# template.net
KiCad netlist of a schematic drawn in Altium Designer
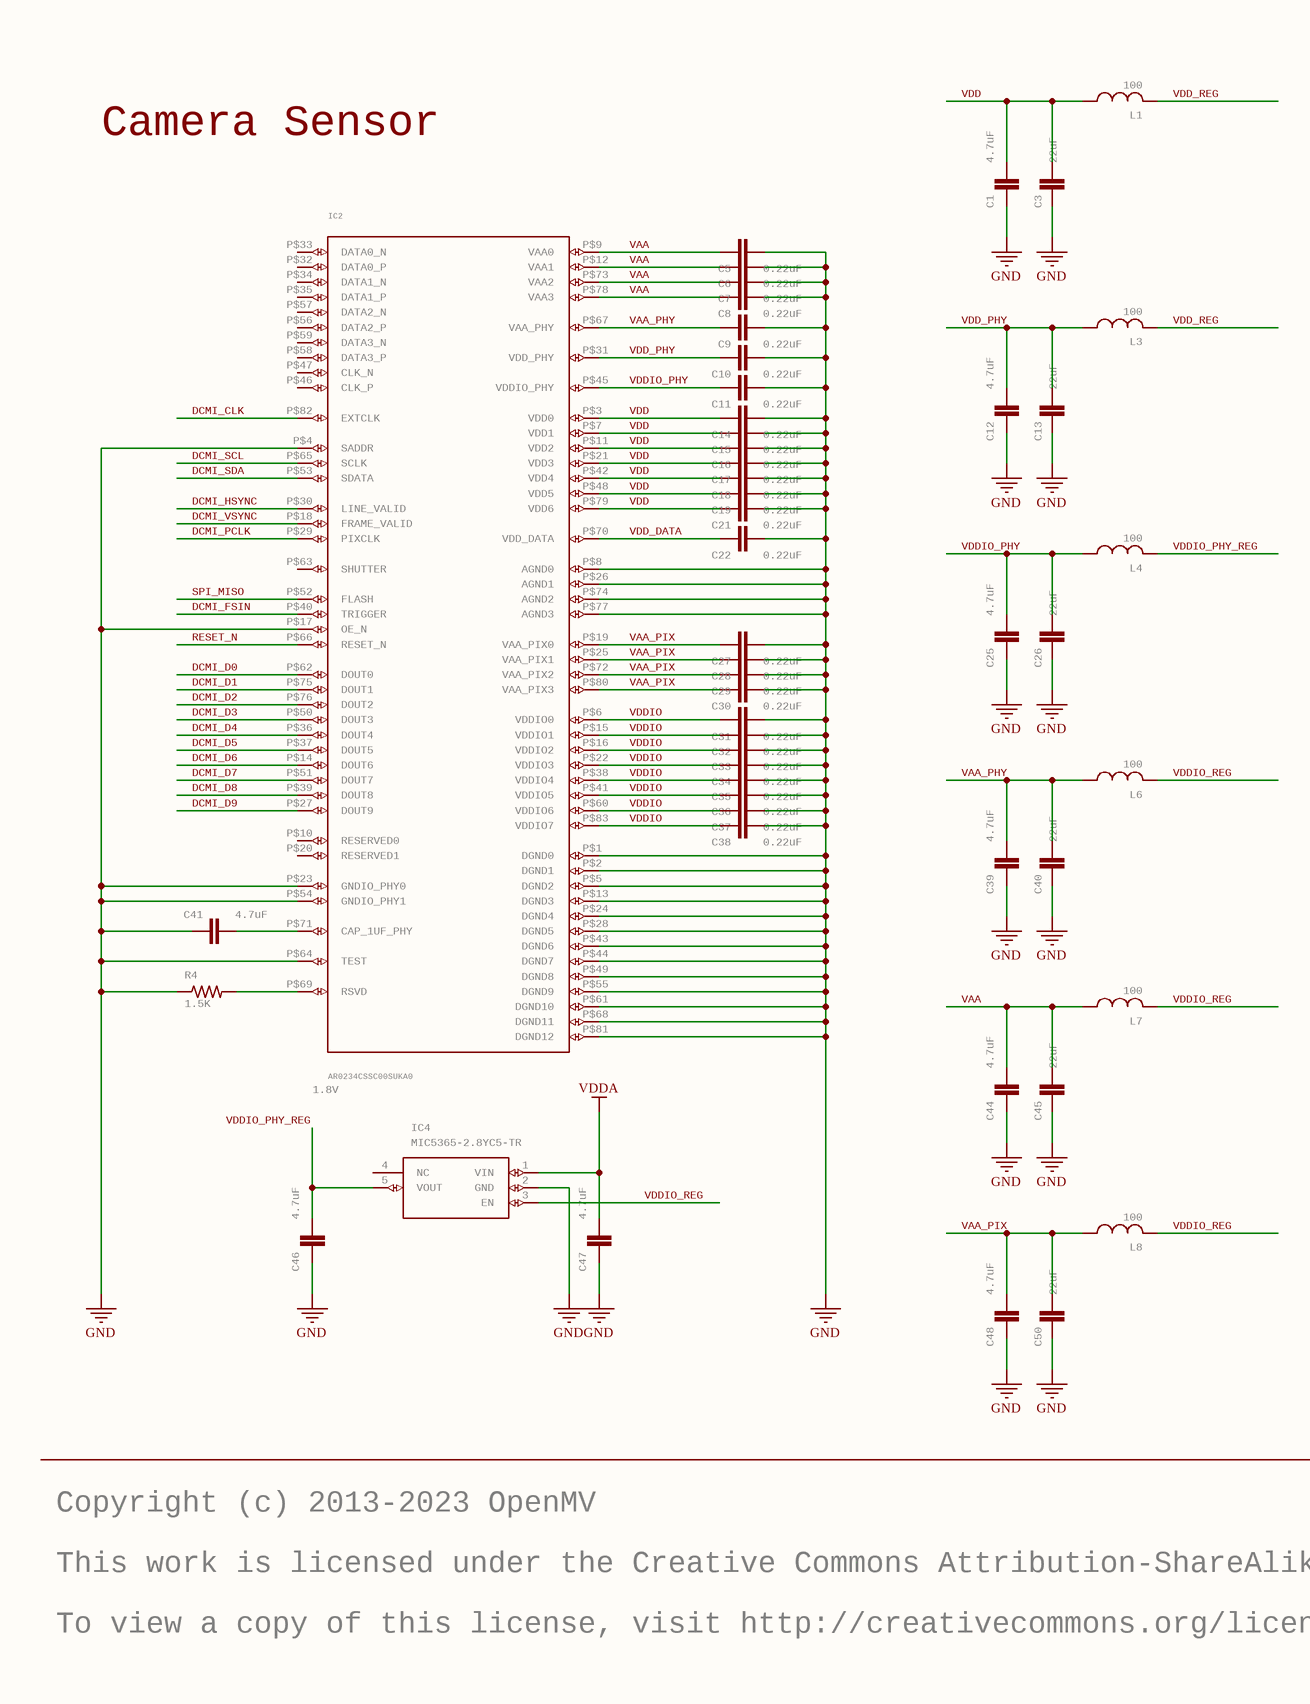
[diagram p0: template.SchDoc, left]
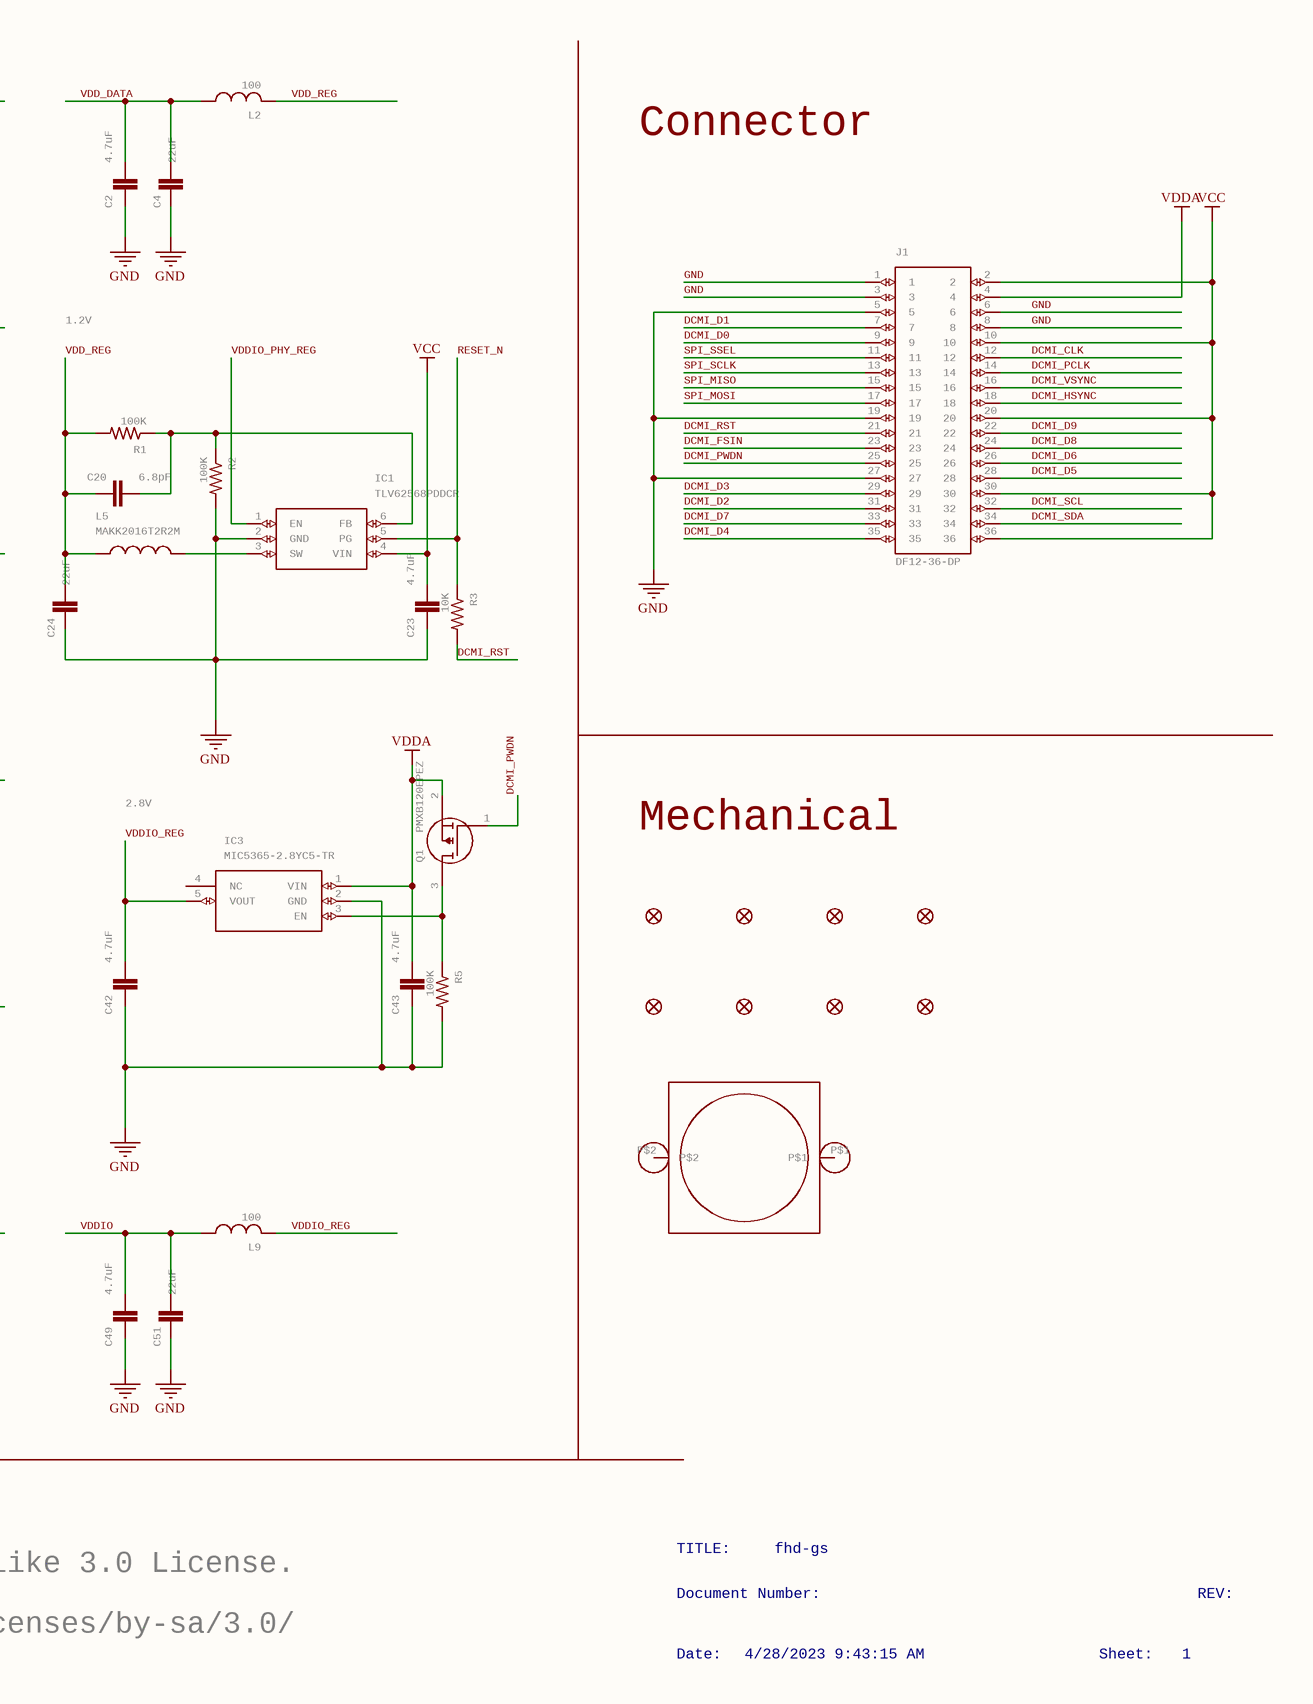
[diagram p1: template.SchDoc, right]

(export (version "E")
  (design (tool "Eeschema 10.0.6"))
  (components
    (comp (ref "C1")
      (value "4.7uF")
      (footprint "0402")
      (description "0402 (1005 Metric) Nick Garner - TeleSense")
      (fields (field (name "MPN") "JMK105BBJ475MV-F"))
      (libsource (lib "") (part "CAP_0402_1"))
    )
    (comp (ref "C2")
      (value "4.7uF")
      (footprint "0402")
      (description "0402 (1005 Metric) Nick Garner - TeleSense")
      (fields (field (name "MPN") "JMK105BBJ475MV-F"))
      (libsource (lib "") (part "CAP_0402_1"))
    )
    (comp (ref "C3")
      (value "22uF")
      (footprint "0805")
      (fields (field (name "MPN") "CL21A226MQQNNNE"))
      (libsource (lib "SparkFun-Capacitors") (part "22UF-0805-6.3V-20%"))
    )
    (comp (ref "C4")
      (value "22uF")
      (footprint "0805")
      (fields (field (name "MPN") "CL21A226MQQNNNE"))
      (libsource (lib "SparkFun-Capacitors") (part "22UF-0805-6.3V-20%"))
    )
    (comp (ref "C5")
      (value "0.22uF")
      (footprint "C0201")
      (description "CAPACITOR, European symbol")
      (fields (field (name "MPN") "GRM033R60J224ME15D"))
      (libsource (lib "rcl") (part "C-EUC0201"))
    )
    (comp (ref "C6")
      (value "0.22uF")
      (footprint "C0201")
      (description "CAPACITOR, European symbol")
      (fields (field (name "MPN") "GRM033R60J224ME15D"))
      (libsource (lib "rcl") (part "C-EUC0201"))
    )
    (comp (ref "C7")
      (value "0.22uF")
      (footprint "C0201")
      (description "CAPACITOR, European symbol")
      (fields (field (name "MPN") "GRM033R60J224ME15D"))
      (libsource (lib "rcl") (part "C-EUC0201"))
    )
    (comp (ref "C8")
      (value "0.22uF")
      (footprint "C0201")
      (description "CAPACITOR, European symbol")
      (fields (field (name "MPN") "GRM033R60J224ME15D"))
      (libsource (lib "rcl") (part "C-EUC0201"))
    )
    (comp (ref "C9")
      (value "0.22uF")
      (footprint "C0201")
      (description "CAPACITOR, European symbol")
      (fields (field (name "MPN") "GRM033R60J224ME15D"))
      (libsource (lib "rcl") (part "C-EUC0201"))
    )
    (comp (ref "C10")
      (value "0.22uF")
      (footprint "C0201")
      (description "CAPACITOR, European symbol")
      (fields (field (name "MPN") "GRM033R60J224ME15D"))
      (libsource (lib "rcl") (part "C-EUC0201"))
    )
    (comp (ref "C11")
      (value "0.22uF")
      (footprint "C0201")
      (description "CAPACITOR, European symbol")
      (fields (field (name "MPN") "GRM033R60J224ME15D"))
      (libsource (lib "rcl") (part "C-EUC0201"))
    )
    (comp (ref "C12")
      (value "4.7uF")
      (footprint "0402")
      (description "0402 (1005 Metric) Nick Garner - TeleSense")
      (fields (field (name "MPN") "JMK105BBJ475MV-F"))
      (libsource (lib "") (part "CAP_0402_1"))
    )
    (comp (ref "C13")
      (value "22uF")
      (footprint "0805")
      (fields (field (name "MPN") "CL21A226MQQNNNE"))
      (libsource (lib "SparkFun-Capacitors") (part "22UF-0805-6.3V-20%"))
    )
    (comp (ref "C14")
      (value "0.22uF")
      (footprint "C0201")
      (description "CAPACITOR, European symbol")
      (fields (field (name "MPN") "GRM033R60J224ME15D"))
      (libsource (lib "rcl") (part "C-EUC0201"))
    )
    (comp (ref "C15")
      (value "0.22uF")
      (footprint "C0201")
      (description "CAPACITOR, European symbol")
      (fields (field (name "MPN") "GRM033R60J224ME15D"))
      (libsource (lib "rcl") (part "C-EUC0201"))
    )
    (comp (ref "C16")
      (value "0.22uF")
      (footprint "C0201")
      (description "CAPACITOR, European symbol")
      (fields (field (name "MPN") "GRM033R60J224ME15D"))
      (libsource (lib "rcl") (part "C-EUC0201"))
    )
    (comp (ref "C17")
      (value "0.22uF")
      (footprint "C0201")
      (description "CAPACITOR, European symbol")
      (fields (field (name "MPN") "GRM033R60J224ME15D"))
      (libsource (lib "rcl") (part "C-EUC0201"))
    )
    (comp (ref "C18")
      (value "0.22uF")
      (footprint "C0201")
      (description "CAPACITOR, European symbol")
      (fields (field (name "MPN") "GRM033R60J224ME15D"))
      (libsource (lib "rcl") (part "C-EUC0201"))
    )
    (comp (ref "C19")
      (value "0.22uF")
      (footprint "C0201")
      (description "CAPACITOR, European symbol")
      (fields (field (name "MPN") "GRM033R60J224ME15D"))
      (libsource (lib "rcl") (part "C-EUC0201"))
    )
    (comp (ref "C20")
      (value "6.8pF")
      (footprint "0402")
      (description "0402 (1005 Metric) Nick Garner - TeleSense")
      (fields (field (name "MPN") "GRM1555C1H6R8DA01D"))
      (libsource (lib "0402") (part "CAP_0402"))
    )
    (comp (ref "C21")
      (value "0.22uF")
      (footprint "C0201")
      (description "CAPACITOR, European symbol")
      (fields (field (name "MPN") "GRM033R60J224ME15D"))
      (libsource (lib "rcl") (part "C-EUC0201"))
    )
    (comp (ref "C22")
      (value "0.22uF")
      (footprint "C0201")
      (description "CAPACITOR, European symbol")
      (fields (field (name "MPN") "GRM033R60J224ME15D"))
      (libsource (lib "rcl") (part "C-EUC0201"))
    )
    (comp (ref "C23")
      (value "4.7uF")
      (footprint "0402")
      (description "0402 (1005 Metric) Nick Garner - TeleSense")
      (fields (field (name "MPN") "JMK105BBJ475MV-F"))
      (libsource (lib "") (part "CAP_0402_1"))
    )
    (comp (ref "C24")
      (value "22uF")
      (footprint "0805")
      (fields (field (name "MPN") "CL21A226MQQNNNE"))
      (libsource (lib "SparkFun-Capacitors") (part "22UF-0805-6.3V-20%"))
    )
    (comp (ref "C25")
      (value "4.7uF")
      (footprint "0402")
      (description "0402 (1005 Metric) Nick Garner - TeleSense")
      (fields (field (name "MPN") "JMK105BBJ475MV-F"))
      (libsource (lib "") (part "CAP_0402_1"))
    )
    (comp (ref "C26")
      (value "22uF")
      (footprint "0805")
      (fields (field (name "MPN") "CL21A226MQQNNNE"))
      (libsource (lib "SparkFun-Capacitors") (part "22UF-0805-6.3V-20%"))
    )
    (comp (ref "C27")
      (value "0.22uF")
      (footprint "C0201")
      (description "CAPACITOR, European symbol")
      (fields (field (name "MPN") "GRM033R60J224ME15D"))
      (libsource (lib "rcl") (part "C-EUC0201"))
    )
    (comp (ref "C28")
      (value "0.22uF")
      (footprint "C0201")
      (description "CAPACITOR, European symbol")
      (fields (field (name "MPN") "GRM033R60J224ME15D"))
      (libsource (lib "rcl") (part "C-EUC0201"))
    )
    (comp (ref "C29")
      (value "0.22uF")
      (footprint "C0201")
      (description "CAPACITOR, European symbol")
      (fields (field (name "MPN") "GRM033R60J224ME15D"))
      (libsource (lib "rcl") (part "C-EUC0201"))
    )
    (comp (ref "C30")
      (value "0.22uF")
      (footprint "C0201")
      (description "CAPACITOR, European symbol")
      (fields (field (name "MPN") "GRM033R60J224ME15D"))
      (libsource (lib "rcl") (part "C-EUC0201"))
    )
    (comp (ref "C31")
      (value "0.22uF")
      (footprint "C0201")
      (description "CAPACITOR, European symbol")
      (fields (field (name "MPN") "GRM033R60J224ME15D"))
      (libsource (lib "rcl") (part "C-EUC0201"))
    )
    (comp (ref "C32")
      (value "0.22uF")
      (footprint "C0201")
      (description "CAPACITOR, European symbol")
      (fields (field (name "MPN") "GRM033R60J224ME15D"))
      (libsource (lib "rcl") (part "C-EUC0201"))
    )
    (comp (ref "C33")
      (value "0.22uF")
      (footprint "C0201")
      (description "CAPACITOR, European symbol")
      (fields (field (name "MPN") "GRM033R60J224ME15D"))
      (libsource (lib "rcl") (part "C-EUC0201"))
    )
    (comp (ref "C34")
      (value "0.22uF")
      (footprint "C0201")
      (description "CAPACITOR, European symbol")
      (fields (field (name "MPN") "GRM033R60J224ME15D"))
      (libsource (lib "rcl") (part "C-EUC0201"))
    )
    (comp (ref "C35")
      (value "0.22uF")
      (footprint "C0201")
      (description "CAPACITOR, European symbol")
      (fields (field (name "MPN") "GRM033R60J224ME15D"))
      (libsource (lib "rcl") (part "C-EUC0201"))
    )
    (comp (ref "C36")
      (value "0.22uF")
      (footprint "C0201")
      (description "CAPACITOR, European symbol")
      (fields (field (name "MPN") "GRM033R60J224ME15D"))
      (libsource (lib "rcl") (part "C-EUC0201"))
    )
    (comp (ref "C37")
      (value "0.22uF")
      (footprint "C0201")
      (description "CAPACITOR, European symbol")
      (fields (field (name "MPN") "GRM033R60J224ME15D"))
      (libsource (lib "rcl") (part "C-EUC0201"))
    )
    (comp (ref "C38")
      (value "0.22uF")
      (footprint "C0201")
      (description "CAPACITOR, European symbol")
      (fields (field (name "MPN") "GRM033R60J224ME15D"))
      (libsource (lib "rcl") (part "C-EUC0201"))
    )
    (comp (ref "C39")
      (value "4.7uF")
      (footprint "0402")
      (description "0402 (1005 Metric) Nick Garner - TeleSense")
      (fields (field (name "MPN") "JMK105BBJ475MV-F"))
      (libsource (lib "") (part "CAP_0402_1"))
    )
    (comp (ref "C40")
      (value "22uF")
      (footprint "0805")
      (fields (field (name "MPN") "CL21A226MQQNNNE"))
      (libsource (lib "SparkFun-Capacitors") (part "22UF-0805-6.3V-20%"))
    )
    (comp (ref "C41")
      (value "4.7uF")
      (footprint "0402")
      (description "0402 (1005 Metric) Nick Garner - TeleSense")
      (fields (field (name "MPN") "JMK105BBJ475MV-F"))
      (libsource (lib "0402") (part "CAP_0402"))
    )
    (comp (ref "C42")
      (value "4.7uF")
      (footprint "0402")
      (description "0402 (1005 Metric) Nick Garner - TeleSense")
      (fields (field (name "MPN") "JMK105BBJ475MV-F"))
      (libsource (lib "") (part "CAP_0402_1"))
    )
    (comp (ref "C43")
      (value "4.7uF")
      (footprint "0402")
      (description "0402 (1005 Metric) Nick Garner - TeleSense")
      (fields (field (name "MPN") "JMK105BBJ475MV-F"))
      (libsource (lib "") (part "CAP_0402_1"))
    )
    (comp (ref "C44")
      (value "4.7uF")
      (footprint "0402")
      (description "0402 (1005 Metric) Nick Garner - TeleSense")
      (fields (field (name "MPN") "JMK105BBJ475MV-F"))
      (libsource (lib "") (part "CAP_0402_1"))
    )
    (comp (ref "C45")
      (value "22uF")
      (footprint "0805")
      (fields (field (name "MPN") "CL21A226MQQNNNE"))
      (libsource (lib "SparkFun-Capacitors") (part "22UF-0805-6.3V-20%"))
    )
    (comp (ref "C46")
      (value "4.7uF")
      (footprint "0402")
      (description "0402 (1005 Metric) Nick Garner - TeleSense")
      (fields (field (name "MPN") "JMK105BBJ475MV-F"))
      (libsource (lib "") (part "CAP_0402_1"))
    )
    (comp (ref "C47")
      (value "4.7uF")
      (footprint "0402")
      (description "0402 (1005 Metric) Nick Garner - TeleSense")
      (fields (field (name "MPN") "JMK105BBJ475MV-F"))
      (libsource (lib "") (part "CAP_0402_1"))
    )
    (comp (ref "C48")
      (value "4.7uF")
      (footprint "0402")
      (description "0402 (1005 Metric) Nick Garner - TeleSense")
      (fields (field (name "MPN") "JMK105BBJ475MV-F"))
      (libsource (lib "") (part "CAP_0402_1"))
    )
    (comp (ref "C49")
      (value "4.7uF")
      (footprint "0402")
      (description "0402 (1005 Metric) Nick Garner - TeleSense")
      (fields (field (name "MPN") "JMK105BBJ475MV-F"))
      (libsource (lib "") (part "CAP_0402_1"))
    )
    (comp (ref "C50")
      (value "22uF")
      (footprint "0805")
      (fields (field (name "MPN") "CL21A226MQQNNNE"))
      (libsource (lib "SparkFun-Capacitors") (part "22UF-0805-6.3V-20%"))
    )
    (comp (ref "C51")
      (value "22uF")
      (footprint "0805")
      (fields (field (name "MPN") "CL21A226MQQNNNE"))
      (libsource (lib "SparkFun-Capacitors") (part "22UF-0805-6.3V-20%"))
    )
    (comp (ref "FD1")
      (value "FIDUCIAL1X2")
      (footprint "FIDUCIAL-1X2")
      (fields (field (name "LIBRARYNAME") "SparkFun-Aesthetics"))
      (libsource (lib "SparkFun-Aesthetics") (part "FIDUCIAL1X2"))
    )
    (comp (ref "FD2")
      (value "FIDUCIAL1X2")
      (footprint "FIDUCIAL-1X2")
      (fields (field (name "LIBRARYNAME") "SparkFun-Aesthetics"))
      (libsource (lib "SparkFun-Aesthetics") (part "FIDUCIAL1X2"))
    )
    (comp (ref "FD3")
      (value "FIDUCIAL1X2")
      (footprint "FIDUCIAL-1X2")
      (fields (field (name "LIBRARYNAME") "SparkFun-Aesthetics"))
      (libsource (lib "SparkFun-Aesthetics") (part "FIDUCIAL1X2"))
    )
    (comp (ref "FD4")
      (value "FIDUCIAL1X2")
      (footprint "FIDUCIAL-1X2")
      (fields (field (name "LIBRARYNAME") "SparkFun-Aesthetics"))
      (libsource (lib "SparkFun-Aesthetics") (part "FIDUCIAL1X2"))
    )
    (comp (ref "FD5")
      (value "FIDUCIAL1X2")
      (footprint "FIDUCIAL-1X2")
      (fields (field (name "LIBRARYNAME") "SparkFun-Aesthetics"))
      (libsource (lib "SparkFun-Aesthetics") (part "FIDUCIAL1X2"))
    )
    (comp (ref "FD6")
      (value "FIDUCIAL1X2")
      (footprint "FIDUCIAL-1X2")
      (fields (field (name "LIBRARYNAME") "SparkFun-Aesthetics"))
      (libsource (lib "SparkFun-Aesthetics") (part "FIDUCIAL1X2"))
    )
    (comp (ref "FD7")
      (value "FIDUCIAL1X2")
      (footprint "FIDUCIAL-1X2")
      (fields (field (name "LIBRARYNAME") "SparkFun-Aesthetics"))
      (libsource (lib "SparkFun-Aesthetics") (part "FIDUCIAL1X2"))
    )
    (comp (ref "FD8")
      (value "FIDUCIAL1X2")
      (footprint "FIDUCIAL-1X2")
      (fields (field (name "LIBRARYNAME") "SparkFun-Aesthetics"))
      (libsource (lib "SparkFun-Aesthetics") (part "FIDUCIAL1X2"))
    )
    (comp (ref "H1")
      (value "LENSMOUNT20MM")
      (footprint "LENSMOUNT-20MM")
      (libsource (lib "lensmount") (part "LENSMOUNT20MM"))
    )
    (comp (ref "IC1")
      (value "TLV62568PDDCR")
      (footprint "SOT95P280X110-6N")
      (description "2.5V-5.5V input, 1A high efficiency step-down buck converter in SOT23 and SOT563 package")
      (fields (field (name "MOUSER_PART_NUMBER") "595-TLV62568PDDCR"))
      (libsource (lib "TLV62568PDDCR") (part "TLV62568PDDCR"))
    )
    (comp (ref "IC2")
      (value "AR0234CSSC00SUKA0")
      (footprint "AR0234CSSC00SUKA0")
      (libsource (lib "AR0234CSSC00SUKA0") (part "AR0234CSSC00SUKA0"))
    )
    (comp (ref "IC3")
      (value "MIC5365-2.8YC5-TR")
      (footprint "SOT65P210X110-5N")
      (description "IC REG LINEAR 2.8V 150MA SC70-5")
      (fields (field (name "MOUSER_PART_NUMBER") "998-MIC5365-2.8YC5TR"))
      (libsource (lib "MIC5365-2.8YC5-TR") (part "MIC5365-2.8YC5-TR"))
    )
    (comp (ref "IC4")
      (value "MIC5365-2.8YC5-TR")
      (footprint "SOT65P210X110-5N")
      (description "IC REG LINEAR 2.8V 150MA SC70-5")
      (fields (field (name "MOUSER_PART_NUMBER") "998-MIC5365-2.8YC5TR"))
      (libsource (lib "MIC5365-2.8YC5-TR") (part "MIC5365-2.8YC5-TR"))
    )
    (comp (ref "J1")
      (value "DF12-36-DP")
      (footprint "DF12-36-DP")
      (fields (field (name "MPN") "DF12NB(3.0)-36DP-0.5V(51)"))
      (libsource (lib "DF12NB(3.0)-36DP-0.5V(51)") (part "DF12-36-DP"))
    )
    (comp (ref "L1")
      (value "100")
      (footprint "0402")
      (fields (field (name "MPN") "MFBM1V1005-101-R"))
      (libsource (lib "0402") (part "INDUCTOR_0402"))
    )
    (comp (ref "L2")
      (value "100")
      (footprint "0402")
      (fields (field (name "MPN") "MFBM1V1005-101-R"))
      (libsource (lib "0402") (part "INDUCTOR_0402"))
    )
    (comp (ref "L3")
      (value "100")
      (footprint "0402")
      (fields (field (name "MPN") "MFBM1V1005-101-R"))
      (libsource (lib "0402") (part "INDUCTOR_0402"))
    )
    (comp (ref "L4")
      (value "100")
      (footprint "0402")
      (fields (field (name "MPN") "MFBM1V1005-101-R"))
      (libsource (lib "0402") (part "INDUCTOR_0402"))
    )
    (comp (ref "L5")
      (value "MAKK2016T2R2M")
      (footprint "INDC2016X100N")
      (description "2.2 µH Shielded Drum Core, Wirewound Inductor 1.5 A 160mOhm Max 0806 (2016 Metric)")
      (fields (field (name "MF") "Taiyo Yuden"))
      (libsource (lib "MAKK2016T2R2M") (part "MAKK2016T2R2M"))
    )
    (comp (ref "L6")
      (value "100")
      (footprint "0402")
      (fields (field (name "MPN") "MFBM1V1005-101-R"))
      (libsource (lib "0402") (part "INDUCTOR_0402"))
    )
    (comp (ref "L7")
      (value "100")
      (footprint "0402")
      (fields (field (name "MPN") "MFBM1V1005-101-R"))
      (libsource (lib "0402") (part "INDUCTOR_0402"))
    )
    (comp (ref "L8")
      (value "100")
      (footprint "0402")
      (fields (field (name "MPN") "MFBM1V1005-101-R"))
      (libsource (lib "0402") (part "INDUCTOR_0402"))
    )
    (comp (ref "L9")
      (value "100")
      (footprint "0402")
      (fields (field (name "MPN") "MFBM1V1005-101-R"))
      (libsource (lib "0402") (part "INDUCTOR_0402"))
    )
    (comp (ref "Q1")
      (value "PMXB120EPEZ")
      (footprint "PMXB120EPEZ")
      (description "MOSFET 30 V, P-channel Trench MOSFET")
      (fields (field (name "MOUSER_PART_NUMBER") "771-PMXB120EPEZ"))
      (libsource (lib "PMXB120EPEZ") (part "PMXB120EPEZ"))
    )
    (comp (ref "R1")
      (value "100K")
      (footprint "R0402")
      (description "RESISTOR, American symbol")
      (fields (field (name "MPN") "AC0402FR-07100KL"))
      (libsource (lib "rcl") (part "R-US_R0402"))
    )
    (comp (ref "R2")
      (value "100K")
      (footprint "R0402")
      (description "RESISTOR, American symbol")
      (fields (field (name "MPN") "AC0402FR-07100KL"))
      (libsource (lib "rcl") (part "R-US_R0402"))
    )
    (comp (ref "R3")
      (value "10K")
      (footprint "R0402")
      (description "RESISTOR, American symbol")
      (fields (field (name "MPN") "AC0402FR-1310KL"))
      (libsource (lib "rcl") (part "R-US_R0402"))
    )
    (comp (ref "R4")
      (value "1.5K")
      (footprint "R0402")
      (description "RESISTOR, American symbol")
      (fields (field (name "MPN") "RC0402FR-131K5L"))
      (libsource (lib "rcl") (part "R-US_R0402"))
    )
    (comp (ref "R5")
      (value "100K")
      (footprint "R0402")
      (description "RESISTOR, American symbol")
      (fields (field (name "MPN") "AC0402FR-07100KL"))
      (libsource (lib "rcl") (part "R-US_R0402"))
    )
  )
  (nets
    (net (code "1") (name "/DCMI_CLK") (class "Default")
      (node (ref "IC2") (pin "P$82") (pinfunction "EXTCLK_P$82") (pintype "bidirectional"))
      (node (ref "J1") (pin "12") (pinfunction "12_12") (pintype "bidirectional"))
    )
    (net (code "2") (name "/DCMI_D0") (class "Default")
      (node (ref "IC2") (pin "P$62") (pinfunction "DOUT0_P$62") (pintype "bidirectional"))
      (node (ref "J1") (pin "9") (pinfunction "9_9") (pintype "bidirectional"))
    )
    (net (code "3") (name "/DCMI_D1") (class "Default")
      (node (ref "IC2") (pin "P$75") (pinfunction "DOUT1_P$75") (pintype "bidirectional"))
      (node (ref "J1") (pin "7") (pinfunction "7_7") (pintype "bidirectional"))
    )
    (net (code "4") (name "/DCMI_D2") (class "Default")
      (node (ref "IC2") (pin "P$76") (pinfunction "DOUT2_P$76") (pintype "bidirectional"))
      (node (ref "J1") (pin "31") (pinfunction "31_31") (pintype "bidirectional"))
    )
    (net (code "5") (name "/DCMI_D3") (class "Default")
      (node (ref "IC2") (pin "P$50") (pinfunction "DOUT3_P$50") (pintype "bidirectional"))
      (node (ref "J1") (pin "29") (pinfunction "29_29") (pintype "bidirectional"))
    )
    (net (code "6") (name "/DCMI_D4") (class "Default")
      (node (ref "IC2") (pin "P$36") (pinfunction "DOUT4_P$36") (pintype "bidirectional"))
      (node (ref "J1") (pin "35") (pinfunction "35_35") (pintype "bidirectional"))
    )
    (net (code "7") (name "/DCMI_D5") (class "Default")
      (node (ref "IC2") (pin "P$37") (pinfunction "DOUT5_P$37") (pintype "bidirectional"))
      (node (ref "J1") (pin "28") (pinfunction "28_28") (pintype "bidirectional"))
    )
    (net (code "8") (name "/DCMI_D6") (class "Default")
      (node (ref "IC2") (pin "P$14") (pinfunction "DOUT6_P$14") (pintype "bidirectional"))
      (node (ref "J1") (pin "26") (pinfunction "26_26") (pintype "bidirectional"))
    )
    (net (code "9") (name "/DCMI_D7") (class "Default")
      (node (ref "IC2") (pin "P$51") (pinfunction "DOUT7_P$51") (pintype "bidirectional"))
      (node (ref "J1") (pin "33") (pinfunction "33_33") (pintype "bidirectional"))
    )
    (net (code "10") (name "/DCMI_D8") (class "Default")
      (node (ref "IC2") (pin "P$39") (pinfunction "DOUT8_P$39") (pintype "bidirectional"))
      (node (ref "J1") (pin "24") (pinfunction "24_24") (pintype "bidirectional"))
    )
    (net (code "11") (name "/DCMI_D9") (class "Default")
      (node (ref "IC2") (pin "P$27") (pinfunction "DOUT9_P$27") (pintype "bidirectional"))
      (node (ref "J1") (pin "22") (pinfunction "22_22") (pintype "bidirectional"))
    )
    (net (code "12") (name "/DCMI_FSIN") (class "Default")
      (node (ref "IC2") (pin "P$40") (pinfunction "TRIGGER_P$40") (pintype "bidirectional"))
      (node (ref "J1") (pin "23") (pinfunction "23_23") (pintype "bidirectional"))
    )
    (net (code "13") (name "/DCMI_HSYNC") (class "Default")
      (node (ref "IC2") (pin "P$30") (pinfunction "LINE_VALID_P$30") (pintype "bidirectional"))
      (node (ref "J1") (pin "18") (pinfunction "18_18") (pintype "bidirectional"))
    )
    (net (code "14") (name "/DCMI_PCLK") (class "Default")
      (node (ref "IC2") (pin "P$29") (pinfunction "PIXCLK_P$29") (pintype "bidirectional"))
      (node (ref "J1") (pin "14") (pinfunction "14_14") (pintype "bidirectional"))
    )
    (net (code "15") (name "/DCMI_PWDN") (class "Default")
      (node (ref "J1") (pin "25") (pinfunction "25_25") (pintype "bidirectional"))
      (node (ref "Q1") (pin "1") (pinfunction "G_1") (pintype "bidirectional"))
    )
    (net (code "16") (name "/DCMI_RST") (class "Default")
      (node (ref "J1") (pin "21") (pinfunction "21_21") (pintype "bidirectional"))
      (node (ref "R3") (pin "2") (pinfunction "2_2") (pintype "passive"))
    )
    (net (code "17") (name "/DCMI_SCL") (class "Default")
      (node (ref "IC2") (pin "P$65") (pinfunction "SCLK_P$65") (pintype "bidirectional"))
      (node (ref "J1") (pin "32") (pinfunction "32_32") (pintype "bidirectional"))
    )
    (net (code "18") (name "/DCMI_SDA") (class "Default")
      (node (ref "IC2") (pin "P$53") (pinfunction "SDATA_P$53") (pintype "bidirectional"))
      (node (ref "J1") (pin "34") (pinfunction "34_34") (pintype "bidirectional"))
    )
    (net (code "19") (name "/DCMI_VSYNC") (class "Default")
      (node (ref "IC2") (pin "P$18") (pinfunction "FRAME_VALID_P$18") (pintype "bidirectional"))
      (node (ref "J1") (pin "16") (pinfunction "16_16") (pintype "bidirectional"))
    )
    (net (code "20") (name "/RESET_N") (class "Default")
      (node (ref "IC1") (pin "5") (pinfunction "PG_5") (pintype "bidirectional"))
      (node (ref "IC2") (pin "P$66") (pinfunction "RESET_N_P$66") (pintype "bidirectional"))
      (node (ref "R3") (pin "1") (pinfunction "1_1") (pintype "passive"))
    )
    (net (code "21") (name "/SPI_MISO") (class "Default")
      (node (ref "IC2") (pin "P$52") (pinfunction "FLASH_P$52") (pintype "bidirectional"))
      (node (ref "J1") (pin "15") (pinfunction "15_15") (pintype "bidirectional"))
    )
    (net (code "22") (name "/SPI_MOSI") (class "Default")
      (node (ref "J1") (pin "17") (pinfunction "17_17") (pintype "bidirectional"))
    )
    (net (code "23") (name "/SPI_SCLK") (class "Default")
      (node (ref "J1") (pin "13") (pinfunction "13_13") (pintype "bidirectional"))
    )
    (net (code "24") (name "/SPI_SSEL") (class "Default")
      (node (ref "J1") (pin "11") (pinfunction "11_11") (pintype "bidirectional"))
    )
    (net (code "25") (name "/VAA") (class "Default")
      (node (ref "C44") (pin "2") (pinfunction "2_2") (pintype "passive"))
      (node (ref "C45") (pin "2") (pinfunction "2_2") (pintype "passive"))
      (node (ref "C5") (pin "1") (pinfunction "1_1") (pintype "passive"))
      (node (ref "C6") (pin "1") (pinfunction "1_1") (pintype "passive"))
      (node (ref "C7") (pin "1") (pinfunction "1_1") (pintype "passive"))
      (node (ref "C8") (pin "1") (pinfunction "1_1") (pintype "passive"))
      (node (ref "IC2") (pin "P$12") (pinfunction "VAA1_P$12") (pintype "bidirectional"))
      (node (ref "IC2") (pin "P$73") (pinfunction "VAA2_P$73") (pintype "bidirectional"))
      (node (ref "IC2") (pin "P$78") (pinfunction "VAA3_P$78") (pintype "bidirectional"))
      (node (ref "IC2") (pin "P$9") (pinfunction "VAA0_P$9") (pintype "bidirectional"))
      (node (ref "L7") (pin "1") (pinfunction "P$1_1") (pintype "passive"))
    )
    (net (code "26") (name "/VAA_PHY") (class "Default")
      (node (ref "C39") (pin "2") (pinfunction "2_2") (pintype "passive"))
      (node (ref "C40") (pin "2") (pinfunction "2_2") (pintype "passive"))
      (node (ref "C9") (pin "1") (pinfunction "1_1") (pintype "passive"))
      (node (ref "IC2") (pin "P$67") (pinfunction "VAA_PHY_P$67") (pintype "bidirectional"))
      (node (ref "L6") (pin "1") (pinfunction "P$1_1") (pintype "passive"))
    )
    (net (code "27") (name "/VAA_PIX") (class "Default")
      (node (ref "C27") (pin "1") (pinfunction "1_1") (pintype "passive"))
      (node (ref "C28") (pin "1") (pinfunction "1_1") (pintype "passive"))
      (node (ref "C29") (pin "1") (pinfunction "1_1") (pintype "passive"))
      (node (ref "C30") (pin "1") (pinfunction "1_1") (pintype "passive"))
      (node (ref "C48") (pin "2") (pinfunction "2_2") (pintype "passive"))
      (node (ref "C50") (pin "2") (pinfunction "2_2") (pintype "passive"))
      (node (ref "IC2") (pin "P$19") (pinfunction "VAA_PIX0_P$19") (pintype "bidirectional"))
      (node (ref "IC2") (pin "P$25") (pinfunction "VAA_PIX1_P$25") (pintype "bidirectional"))
      (node (ref "IC2") (pin "P$72") (pinfunction "VAA_PIX2_P$72") (pintype "bidirectional"))
      (node (ref "IC2") (pin "P$80") (pinfunction "VAA_PIX3_P$80") (pintype "bidirectional"))
      (node (ref "L8") (pin "1") (pinfunction "P$1_1") (pintype "passive"))
    )
    (net (code "28") (name "/VDD") (class "Default")
      (node (ref "C1") (pin "2") (pinfunction "2_2") (pintype "passive"))
      (node (ref "C14") (pin "1") (pinfunction "1_1") (pintype "passive"))
      (node (ref "C15") (pin "1") (pinfunction "1_1") (pintype "passive"))
      (node (ref "C16") (pin "1") (pinfunction "1_1") (pintype "passive"))
      (node (ref "C17") (pin "1") (pinfunction "1_1") (pintype "passive"))
      (node (ref "C18") (pin "1") (pinfunction "1_1") (pintype "passive"))
      (node (ref "C19") (pin "1") (pinfunction "1_1") (pintype "passive"))
      (node (ref "C21") (pin "1") (pinfunction "1_1") (pintype "passive"))
      (node (ref "C3") (pin "2") (pinfunction "2_2") (pintype "passive"))
      (node (ref "IC2") (pin "P$11") (pinfunction "VDD2_P$11") (pintype "bidirectional"))
      (node (ref "IC2") (pin "P$21") (pinfunction "VDD3_P$21") (pintype "bidirectional"))
      (node (ref "IC2") (pin "P$3") (pinfunction "VDD0_P$3") (pintype "bidirectional"))
      (node (ref "IC2") (pin "P$42") (pinfunction "VDD4_P$42") (pintype "bidirectional"))
      (node (ref "IC2") (pin "P$48") (pinfunction "VDD5_P$48") (pintype "bidirectional"))
      (node (ref "IC2") (pin "P$7") (pinfunction "VDD1_P$7") (pintype "bidirectional"))
      (node (ref "IC2") (pin "P$79") (pinfunction "VDD6_P$79") (pintype "bidirectional"))
      (node (ref "L1") (pin "1") (pinfunction "P$1_1") (pintype "passive"))
    )
    (net (code "29") (name "/VDDIO") (class "Default")
      (node (ref "C31") (pin "1") (pinfunction "1_1") (pintype "passive"))
      (node (ref "C32") (pin "1") (pinfunction "1_1") (pintype "passive"))
      (node (ref "C33") (pin "1") (pinfunction "1_1") (pintype "passive"))
      (node (ref "C34") (pin "1") (pinfunction "1_1") (pintype "passive"))
      (node (ref "C35") (pin "1") (pinfunction "1_1") (pintype "passive"))
      (node (ref "C36") (pin "1") (pinfunction "1_1") (pintype "passive"))
      (node (ref "C37") (pin "1") (pinfunction "1_1") (pintype "passive"))
      (node (ref "C38") (pin "1") (pinfunction "1_1") (pintype "passive"))
      (node (ref "C49") (pin "2") (pinfunction "2_2") (pintype "passive"))
      (node (ref "C51") (pin "2") (pinfunction "2_2") (pintype "passive"))
      (node (ref "IC2") (pin "P$15") (pinfunction "VDDIO1_P$15") (pintype "bidirectional"))
      (node (ref "IC2") (pin "P$16") (pinfunction "VDDIO2_P$16") (pintype "bidirectional"))
      (node (ref "IC2") (pin "P$22") (pinfunction "VDDIO3_P$22") (pintype "bidirectional"))
      (node (ref "IC2") (pin "P$38") (pinfunction "VDDIO4_P$38") (pintype "bidirectional"))
      (node (ref "IC2") (pin "P$41") (pinfunction "VDDIO5_P$41") (pintype "bidirectional"))
      (node (ref "IC2") (pin "P$6") (pinfunction "VDDIO0_P$6") (pintype "bidirectional"))
      (node (ref "IC2") (pin "P$60") (pinfunction "VDDIO6_P$60") (pintype "bidirectional"))
      (node (ref "IC2") (pin "P$83") (pinfunction "VDDIO7_P$83") (pintype "bidirectional"))
      (node (ref "L9") (pin "1") (pinfunction "P$1_1") (pintype "passive"))
    )
    (net (code "30") (name "/VDDIO_PHY") (class "Default")
      (node (ref "C11") (pin "1") (pinfunction "1_1") (pintype "passive"))
      (node (ref "C25") (pin "2") (pinfunction "2_2") (pintype "passive"))
      (node (ref "C26") (pin "2") (pinfunction "2_2") (pintype "passive"))
      (node (ref "IC2") (pin "P$45") (pinfunction "VDDIO_PHY_P$45") (pintype "bidirectional"))
      (node (ref "L4") (pin "1") (pinfunction "P$1_1") (pintype "passive"))
    )
    (net (code "31") (name "/VDDIO_PHY_REG") (class "Default")
      (node (ref "C46") (pin "2") (pinfunction "2_2") (pintype "passive"))
      (node (ref "IC1") (pin "1") (pinfunction "EN_1") (pintype "bidirectional"))
      (node (ref "IC4") (pin "5") (pinfunction "VOUT_5") (pintype "bidirectional"))
      (node (ref "L4") (pin "2") (pinfunction "P$2_2") (pintype "passive"))
    )
    (net (code "32") (name "/VDDIO_REG") (class "Default")
      (node (ref "C42") (pin "2") (pinfunction "2_2") (pintype "passive"))
      (node (ref "IC3") (pin "5") (pinfunction "VOUT_5") (pintype "bidirectional"))
      (node (ref "IC4") (pin "3") (pinfunction "EN_3") (pintype "bidirectional"))
      (node (ref "L6") (pin "2") (pinfunction "P$2_2") (pintype "passive"))
      (node (ref "L7") (pin "2") (pinfunction "P$2_2") (pintype "passive"))
      (node (ref "L8") (pin "2") (pinfunction "P$2_2") (pintype "passive"))
      (node (ref "L9") (pin "2") (pinfunction "P$2_2") (pintype "passive"))
    )
    (net (code "33") (name "/VDD_DATA") (class "Default")
      (node (ref "C2") (pin "2") (pinfunction "2_2") (pintype "passive"))
      (node (ref "C22") (pin "1") (pinfunction "1_1") (pintype "passive"))
      (node (ref "C4") (pin "2") (pinfunction "2_2") (pintype "passive"))
      (node (ref "IC2") (pin "P$70") (pinfunction "VDD_DATA_P$70") (pintype "bidirectional"))
      (node (ref "L2") (pin "1") (pinfunction "P$1_1") (pintype "passive"))
    )
    (net (code "34") (name "/VDD_PHY") (class "Default")
      (node (ref "C10") (pin "1") (pinfunction "1_1") (pintype "passive"))
      (node (ref "C12") (pin "2") (pinfunction "2_2") (pintype "passive"))
      (node (ref "C13") (pin "2") (pinfunction "2_2") (pintype "passive"))
      (node (ref "IC2") (pin "P$31") (pinfunction "VDD_PHY_P$31") (pintype "bidirectional"))
      (node (ref "L3") (pin "1") (pinfunction "P$1_1") (pintype "passive"))
    )
    (net (code "35") (name "/VDD_REG") (class "Default")
      (node (ref "C20") (pin "1") (pinfunction "1_1") (pintype "passive"))
      (node (ref "C24") (pin "2") (pinfunction "2_2") (pintype "passive"))
      (node (ref "L1") (pin "2") (pinfunction "P$2_2") (pintype "passive"))
      (node (ref "L2") (pin "2") (pinfunction "P$2_2") (pintype "passive"))
      (node (ref "L3") (pin "2") (pinfunction "P$2_2") (pintype "passive"))
      (node (ref "L5") (pin "1") (pinfunction "1_1") (pintype "passive"))
      (node (ref "R1") (pin "2") (pinfunction "2_2") (pintype "passive"))
    )
    (net (code "36") (name "GND") (class "Default")
      (node (ref "C1") (pin "1") (pinfunction "1_1") (pintype "passive"))
      (node (ref "C10") (pin "2") (pinfunction "2_2") (pintype "passive"))
      (node (ref "C11") (pin "2") (pinfunction "2_2") (pintype "passive"))
      (node (ref "C12") (pin "1") (pinfunction "1_1") (pintype "passive"))
      (node (ref "C13") (pin "1") (pinfunction "1_1") (pintype "passive"))
      (node (ref "C14") (pin "2") (pinfunction "2_2") (pintype "passive"))
      (node (ref "C15") (pin "2") (pinfunction "2_2") (pintype "passive"))
      (node (ref "C16") (pin "2") (pinfunction "2_2") (pintype "passive"))
      (node (ref "C17") (pin "2") (pinfunction "2_2") (pintype "passive"))
      (node (ref "C18") (pin "2") (pinfunction "2_2") (pintype "passive"))
      (node (ref "C19") (pin "2") (pinfunction "2_2") (pintype "passive"))
      (node (ref "C2") (pin "1") (pinfunction "1_1") (pintype "passive"))
      (node (ref "C21") (pin "2") (pinfunction "2_2") (pintype "passive"))
      (node (ref "C22") (pin "2") (pinfunction "2_2") (pintype "passive"))
      (node (ref "C23") (pin "1") (pinfunction "1_1") (pintype "passive"))
      (node (ref "C24") (pin "1") (pinfunction "1_1") (pintype "passive"))
      (node (ref "C25") (pin "1") (pinfunction "1_1") (pintype "passive"))
      (node (ref "C26") (pin "1") (pinfunction "1_1") (pintype "passive"))
      (node (ref "C27") (pin "2") (pinfunction "2_2") (pintype "passive"))
      (node (ref "C28") (pin "2") (pinfunction "2_2") (pintype "passive"))
      (node (ref "C29") (pin "2") (pinfunction "2_2") (pintype "passive"))
      (node (ref "C3") (pin "1") (pinfunction "1_1") (pintype "passive"))
      (node (ref "C30") (pin "2") (pinfunction "2_2") (pintype "passive"))
      (node (ref "C31") (pin "2") (pinfunction "2_2") (pintype "passive"))
      (node (ref "C32") (pin "2") (pinfunction "2_2") (pintype "passive"))
      (node (ref "C33") (pin "2") (pinfunction "2_2") (pintype "passive"))
      (node (ref "C34") (pin "2") (pinfunction "2_2") (pintype "passive"))
      (node (ref "C35") (pin "2") (pinfunction "2_2") (pintype "passive"))
      (node (ref "C36") (pin "2") (pinfunction "2_2") (pintype "passive"))
      (node (ref "C37") (pin "2") (pinfunction "2_2") (pintype "passive"))
      (node (ref "C38") (pin "2") (pinfunction "2_2") (pintype "passive"))
      (node (ref "C39") (pin "1") (pinfunction "1_1") (pintype "passive"))
      (node (ref "C4") (pin "1") (pinfunction "1_1") (pintype "passive"))
      (node (ref "C40") (pin "1") (pinfunction "1_1") (pintype "passive"))
      (node (ref "C41") (pin "1") (pinfunction "1_1") (pintype "passive"))
      (node (ref "C42") (pin "1") (pinfunction "1_1") (pintype "passive"))
      (node (ref "C43") (pin "1") (pinfunction "1_1") (pintype "passive"))
      (node (ref "C44") (pin "1") (pinfunction "1_1") (pintype "passive"))
      (node (ref "C45") (pin "1") (pinfunction "1_1") (pintype "passive"))
      (node (ref "C46") (pin "1") (pinfunction "1_1") (pintype "passive"))
      (node (ref "C47") (pin "1") (pinfunction "1_1") (pintype "passive"))
      (node (ref "C48") (pin "1") (pinfunction "1_1") (pintype "passive"))
      (node (ref "C49") (pin "1") (pinfunction "1_1") (pintype "passive"))
      (node (ref "C5") (pin "2") (pinfunction "2_2") (pintype "passive"))
      (node (ref "C50") (pin "1") (pinfunction "1_1") (pintype "passive"))
      (node (ref "C51") (pin "1") (pinfunction "1_1") (pintype "passive"))
      (node (ref "C6") (pin "2") (pinfunction "2_2") (pintype "passive"))
      (node (ref "C7") (pin "2") (pinfunction "2_2") (pintype "passive"))
      (node (ref "C8") (pin "2") (pinfunction "2_2") (pintype "passive"))
      (node (ref "C9") (pin "2") (pinfunction "2_2") (pintype "passive"))
      (node (ref "IC1") (pin "2") (pinfunction "GND_2") (pintype "bidirectional"))
      (node (ref "IC2") (pin "P$1") (pinfunction "DGND0_P$1") (pintype "bidirectional"))
      (node (ref "IC2") (pin "P$13") (pinfunction "DGND3_P$13") (pintype "bidirectional"))
      (node (ref "IC2") (pin "P$17") (pinfunction "OE_N_P$17") (pintype "bidirectional"))
      (node (ref "IC2") (pin "P$2") (pinfunction "DGND1_P$2") (pintype "bidirectional"))
      (node (ref "IC2") (pin "P$23") (pinfunction "GNDIO_PHY0_P$23") (pintype "bidirectional"))
      (node (ref "IC2") (pin "P$24") (pinfunction "DGND4_P$24") (pintype "bidirectional"))
      (node (ref "IC2") (pin "P$26") (pinfunction "AGND1_P$26") (pintype "bidirectional"))
      (node (ref "IC2") (pin "P$28") (pinfunction "DGND5_P$28") (pintype "bidirectional"))
      (node (ref "IC2") (pin "P$4") (pinfunction "SADDR_P$4") (pintype "bidirectional"))
      (node (ref "IC2") (pin "P$43") (pinfunction "DGND6_P$43") (pintype "bidirectional"))
      (node (ref "IC2") (pin "P$44") (pinfunction "DGND7_P$44") (pintype "bidirectional"))
      (node (ref "IC2") (pin "P$49") (pinfunction "DGND8_P$49") (pintype "bidirectional"))
      (node (ref "IC2") (pin "P$5") (pinfunction "DGND2_P$5") (pintype "bidirectional"))
      (node (ref "IC2") (pin "P$54") (pinfunction "GNDIO_PHY1_P$54") (pintype "bidirectional"))
      (node (ref "IC2") (pin "P$55") (pinfunction "DGND9_P$55") (pintype "bidirectional"))
      (node (ref "IC2") (pin "P$61") (pinfunction "DGND10_P$61") (pintype "bidirectional"))
      (node (ref "IC2") (pin "P$64") (pinfunction "TEST_P$64") (pintype "bidirectional"))
      (node (ref "IC2") (pin "P$68") (pinfunction "DGND11_P$68") (pintype "bidirectional"))
      (node (ref "IC2") (pin "P$74") (pinfunction "AGND2_P$74") (pintype "bidirectional"))
      (node (ref "IC2") (pin "P$77") (pinfunction "AGND3_P$77") (pintype "bidirectional"))
      (node (ref "IC2") (pin "P$8") (pinfunction "AGND0_P$8") (pintype "bidirectional"))
      (node (ref "IC2") (pin "P$81") (pinfunction "DGND12_P$81") (pintype "bidirectional"))
      (node (ref "IC3") (pin "2") (pinfunction "GND_2") (pintype "bidirectional"))
      (node (ref "IC4") (pin "2") (pinfunction "GND_2") (pintype "bidirectional"))
      (node (ref "J1") (pin "1") (pinfunction "1_1") (pintype "bidirectional"))
      (node (ref "J1") (pin "19") (pinfunction "19_19") (pintype "bidirectional"))
      (node (ref "J1") (pin "27") (pinfunction "27_27") (pintype "bidirectional"))
      (node (ref "J1") (pin "3") (pinfunction "3_3") (pintype "bidirectional"))
      (node (ref "J1") (pin "5") (pinfunction "5_5") (pintype "bidirectional"))
      (node (ref "J1") (pin "6") (pinfunction "6_6") (pintype "bidirectional"))
      (node (ref "J1") (pin "8") (pinfunction "8_8") (pintype "bidirectional"))
      (node (ref "R2") (pin "2") (pinfunction "2_2") (pintype "passive"))
      (node (ref "R4") (pin "1") (pinfunction "1_1") (pintype "passive"))
      (node (ref "R5") (pin "2") (pinfunction "2_2") (pintype "passive"))
    )
    (net (code "37") (name "Net-(IC1-FB)") (class "Default")
      (node (ref "C20") (pin "2") (pinfunction "2_2") (pintype "passive"))
      (node (ref "IC1") (pin "6") (pinfunction "FB_6") (pintype "bidirectional"))
      (node (ref "R1") (pin "1") (pinfunction "1_1") (pintype "passive"))
      (node (ref "R2") (pin "1") (pinfunction "1_1") (pintype "passive"))
    )
    (net (code "38") (name "Net-(IC1-SW)") (class "Default")
      (node (ref "IC1") (pin "3") (pinfunction "SW_3") (pintype "bidirectional"))
      (node (ref "L5") (pin "2") (pinfunction "2_2") (pintype "passive"))
    )
    (net (code "39") (name "Net-(IC2-CAP_1UF_PHY)") (class "Default")
      (node (ref "C41") (pin "2") (pinfunction "2_2") (pintype "passive"))
      (node (ref "IC2") (pin "P$71") (pinfunction "CAP_1UF_PHY_P$71") (pintype "bidirectional"))
    )
    (net (code "40") (name "Net-(IC2-RSVD)") (class "Default")
      (node (ref "IC2") (pin "P$69") (pinfunction "RSVD_P$69") (pintype "bidirectional"))
      (node (ref "R4") (pin "2") (pinfunction "2_2") (pintype "passive"))
    )
    (net (code "41") (name "Net-(IC3-EN)") (class "Default")
      (node (ref "IC3") (pin "3") (pinfunction "EN_3") (pintype "bidirectional"))
      (node (ref "Q1") (pin "3") (pinfunction "D_3") (pintype "bidirectional"))
      (node (ref "R5") (pin "1") (pinfunction "1_1") (pintype "passive"))
    )
    (net (code "42") (name "VCC") (class "Default")
      (node (ref "C23") (pin "2") (pinfunction "2_2") (pintype "passive"))
      (node (ref "IC1") (pin "4") (pinfunction "VIN_4") (pintype "bidirectional"))
      (node (ref "J1") (pin "10") (pinfunction "10_10") (pintype "bidirectional"))
      (node (ref "J1") (pin "2") (pinfunction "2_2") (pintype "bidirectional"))
      (node (ref "J1") (pin "20") (pinfunction "20_20") (pintype "bidirectional"))
      (node (ref "J1") (pin "30") (pinfunction "30_30") (pintype "bidirectional"))
      (node (ref "J1") (pin "36") (pinfunction "36_36") (pintype "bidirectional"))
    )
    (net (code "43") (name "VDDA") (class "Default")
      (node (ref "C43") (pin "2") (pinfunction "2_2") (pintype "passive"))
      (node (ref "C47") (pin "2") (pinfunction "2_2") (pintype "passive"))
      (node (ref "IC3") (pin "1") (pinfunction "VIN_1") (pintype "bidirectional"))
      (node (ref "IC4") (pin "1") (pinfunction "VIN_1") (pintype "bidirectional"))
      (node (ref "J1") (pin "4") (pinfunction "4_4") (pintype "bidirectional"))
      (node (ref "Q1") (pin "2") (pinfunction "S_2") (pintype "bidirectional"))
    )
    (net (code "44") (name "unconnected-(H1-PadP$1)") (class "Default")
      (node (ref "H1") (pin "P$1") (pinfunction "P$1_P$1") (pintype "power_in"))
    )
    (net (code "45") (name "unconnected-(H1-PadP$2)") (class "Default")
      (node (ref "H1") (pin "P$2") (pinfunction "P$2_P$2") (pintype "power_in"))
    )
    (net (code "46") (name "unconnected-(IC2-CLK_N-PadP$47)") (class "Default")
      (node (ref "IC2") (pin "P$47") (pinfunction "CLK_N_P$47") (pintype "bidirectional"))
    )
    (net (code "47") (name "unconnected-(IC2-CLK_P-PadP$46)") (class "Default")
      (node (ref "IC2") (pin "P$46") (pinfunction "CLK_P_P$46") (pintype "bidirectional"))
    )
    (net (code "48") (name "unconnected-(IC2-DATA0_N-PadP$33)") (class "Default")
      (node (ref "IC2") (pin "P$33") (pinfunction "DATA0_N_P$33") (pintype "bidirectional"))
    )
    (net (code "49") (name "unconnected-(IC2-DATA0_P-PadP$32)") (class "Default")
      (node (ref "IC2") (pin "P$32") (pinfunction "DATA0_P_P$32") (pintype "bidirectional"))
    )
    (net (code "50") (name "unconnected-(IC2-DATA1_N-PadP$34)") (class "Default")
      (node (ref "IC2") (pin "P$34") (pinfunction "DATA1_N_P$34") (pintype "bidirectional"))
    )
    (net (code "51") (name "unconnected-(IC2-DATA1_P-PadP$35)") (class "Default")
      (node (ref "IC2") (pin "P$35") (pinfunction "DATA1_P_P$35") (pintype "bidirectional"))
    )
    (net (code "52") (name "unconnected-(IC2-DATA2_N-PadP$57)") (class "Default")
      (node (ref "IC2") (pin "P$57") (pinfunction "DATA2_N_P$57") (pintype "bidirectional"))
    )
    (net (code "53") (name "unconnected-(IC2-DATA2_P-PadP$56)") (class "Default")
      (node (ref "IC2") (pin "P$56") (pinfunction "DATA2_P_P$56") (pintype "bidirectional"))
    )
    (net (code "54") (name "unconnected-(IC2-DATA3_N-PadP$59)") (class "Default")
      (node (ref "IC2") (pin "P$59") (pinfunction "DATA3_N_P$59") (pintype "bidirectional"))
    )
    (net (code "55") (name "unconnected-(IC2-DATA3_P-PadP$58)") (class "Default")
      (node (ref "IC2") (pin "P$58") (pinfunction "DATA3_P_P$58") (pintype "bidirectional"))
    )
    (net (code "56") (name "unconnected-(IC2-RESERVED0-PadP$10)") (class "Default")
      (node (ref "IC2") (pin "P$10") (pinfunction "RESERVED0_P$10") (pintype "bidirectional"))
    )
    (net (code "57") (name "unconnected-(IC2-RESERVED1-PadP$20)") (class "Default")
      (node (ref "IC2") (pin "P$20") (pinfunction "RESERVED1_P$20") (pintype "bidirectional"))
    )
    (net (code "58") (name "unconnected-(IC2-SHUTTER-PadP$63)") (class "Default")
      (node (ref "IC2") (pin "P$63") (pinfunction "SHUTTER_P$63") (pintype "bidirectional"))
    )
    (net (code "59") (name "unconnected-(IC3-NC-Pad4)") (class "Default")
      (node (ref "IC3") (pin "4") (pinfunction "NC_4") (pintype "passive"))
    )
    (net (code "60") (name "unconnected-(IC4-NC-Pad4)") (class "Default")
      (node (ref "IC4") (pin "4") (pinfunction "NC_4") (pintype "passive"))
    )
  )
)
